# 11_5V_RAIL_ADC.net
KiCad netlist of a schematic drawn in Altium Designer
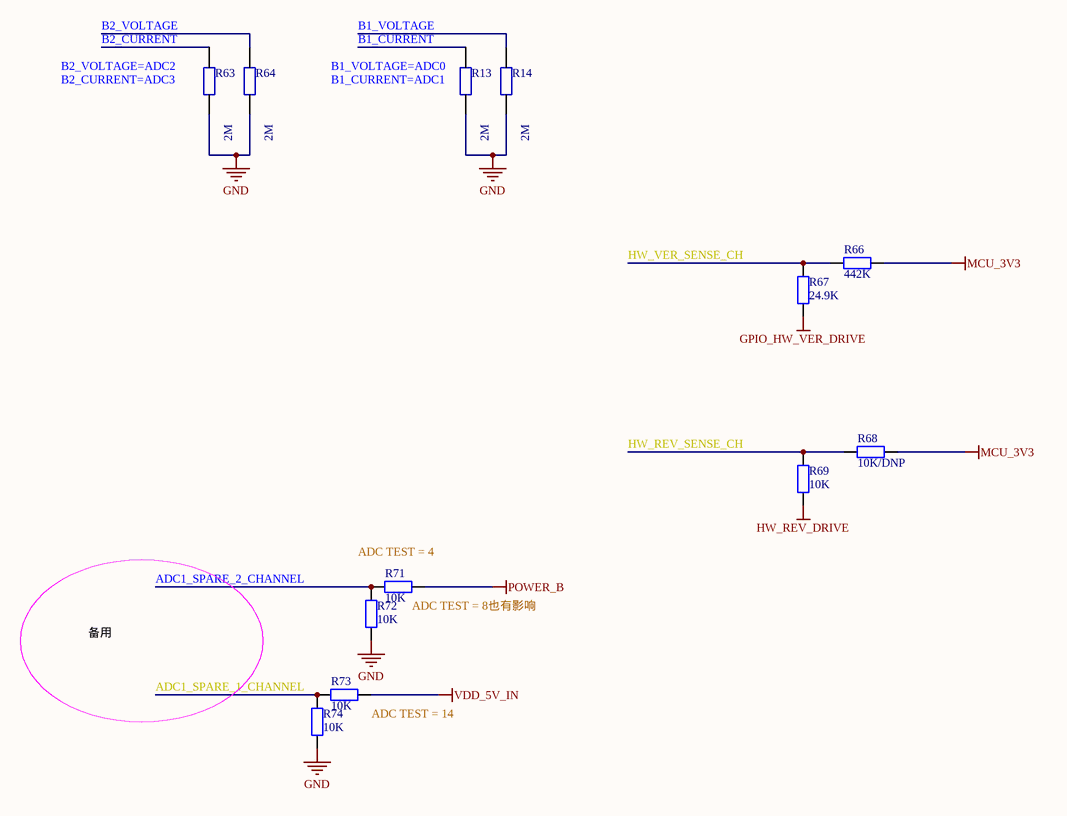
[diagram p0: 11_5V_RAIL_ADC.SchDoc]

(export (version "E")
  (design (tool "Eeschema 10.0.6"))
  (components
    (comp (ref "R13")
      (value "2M")
      (footprint "0402R")
      (description "0402R10K 1%")
      (libsource (lib "CUAV") (part "0402R10K"))
    )
    (comp (ref "R14")
      (value "2M")
      (footprint "0402R")
      (description "0402R10K 1%")
      (libsource (lib "CUAV") (part "0402R10K"))
    )
    (comp (ref "R63")
      (value "2M")
      (footprint "0402R")
      (description "0402R10K 1%")
      (libsource (lib "CUAV") (part "0402R10K"))
    )
    (comp (ref "R64")
      (value "2M")
      (footprint "0402R")
      (description "0402R10K 1%")
      (libsource (lib "CUAV") (part "0402R10K"))
    )
    (comp (ref "R66")
      (value "442K")
      (description "Resistor")
      (fields (field (name "PUBLISHER") "Altium Limited"))
      (libsource (lib "") (part "Res2_1"))
    )
    (comp (ref "R67")
      (value "24.9K")
      (description "Resistor")
      (fields (field (name "PUBLISHER") "Altium Limited"))
      (libsource (lib "Miscellaneous Devices") (part "Res2"))
    )
    (comp (ref "R68")
      (value "10K/DNP")
      (description "Resistor")
      (fields (field (name "PUBLISHER") "Altium Limited"))
      (libsource (lib "") (part "Res2_1"))
    )
    (comp (ref "R69")
      (value "10K")
      (description "Resistor")
      (fields (field (name "PUBLISHER") "Altium Limited"))
      (libsource (lib "Miscellaneous Devices") (part "Res2"))
    )
    (comp (ref "R71")
      (value "10K")
      (description "Resistor")
      (fields (field (name "PUBLISHER") "Altium Limited"))
      (libsource (lib "") (part "Res2_1"))
    )
    (comp (ref "R72")
      (value "10K")
      (description "Resistor")
      (fields (field (name "PUBLISHER") "Altium Limited"))
      (libsource (lib "Miscellaneous Devices") (part "Res2"))
    )
    (comp (ref "R73")
      (value "10K")
      (description "Resistor")
      (fields (field (name "PUBLISHER") "Altium Limited"))
      (libsource (lib "") (part "Res2_1"))
    )
    (comp (ref "R74")
      (value "10K")
      (description "Resistor")
      (fields (field (name "PUBLISHER") "Altium Limited"))
      (libsource (lib "Miscellaneous Devices") (part "Res2"))
    )
  )
  (nets
    (net (code "4") (name "/ADC1_SPARE_1_CHANNEL") (class "Default")
      (node (ref "R73") (pin "1") (pinfunction "1_1") (pintype "passive"))
      (node (ref "R74") (pin "2") (pinfunction "2_2") (pintype "passive"))
    )
    (net (code "5") (name "/ADC1_SPARE_2_CHANNEL") (class "Default")
      (node (ref "R71") (pin "1") (pinfunction "1_1") (pintype "passive"))
      (node (ref "R72") (pin "2") (pinfunction "2_2") (pintype "passive"))
    )
    (net (code "6") (name "/B1_CURRENT") (class "Default") (node (ref "R13") (pin "1") (pintype "passive")))
    (net (code "8") (name "/B1_VOLTAGE") (class "Default") (node (ref "R14") (pin "1") (pintype "passive")))
    (net (code "10") (name "/B2_CURRENT") (class "Default") (node (ref "R63") (pin "1") (pintype "passive")))
    (net (code "12") (name "/B2_VOLTAGE") (class "Default") (node (ref "R64") (pin "1") (pintype "passive")))
    (net (code "14") (name "/HW_REV_SENSE_CH") (class "Default")
      (node (ref "R68") (pin "1") (pinfunction "1_1") (pintype "passive"))
      (node (ref "R69") (pin "2") (pinfunction "2_2") (pintype "passive"))
    )
    (net (code "15") (name "/HW_VER_SENSE_CH") (class "Default")
      (node (ref "R66") (pin "1") (pinfunction "1_1") (pintype "passive"))
      (node (ref "R67") (pin "2") (pinfunction "2_2") (pintype "passive"))
    )
    (net (code "17") (name "GND") (class "Default")
      (node (ref "R13") (pin "2") (pintype "passive"))
      (node (ref "R14") (pin "2") (pintype "passive"))
      (node (ref "R63") (pin "2") (pintype "passive"))
      (node (ref "R64") (pin "2") (pintype "passive"))
      (node (ref "R72") (pin "1") (pinfunction "1_1") (pintype "passive"))
      (node (ref "R74") (pin "1") (pinfunction "1_1") (pintype "passive"))
    )
    (net (code "18") (name "GPIO_HW_VER_DRIVE") (class "Default")
      (node (ref "R67") (pin "1") (pinfunction "1_1") (pintype "passive"))
    )
    (net (code "19") (name "HW_REV_DRIVE") (class "Default")
      (node (ref "R69") (pin "1") (pinfunction "1_1") (pintype "passive"))
    )
    (net (code "20") (name "MCU_3V3") (class "Default")
      (node (ref "R66") (pin "2") (pinfunction "2_2") (pintype "passive"))
      (node (ref "R68") (pin "2") (pinfunction "2_2") (pintype "passive"))
    )
    (net (code "21") (name "POWER_B") (class "Default")
      (node (ref "R71") (pin "2") (pinfunction "2_2") (pintype "passive"))
    )
    (net (code "22") (name "VDD_5V_IN") (class "Default")
      (node (ref "R73") (pin "2") (pinfunction "2_2") (pintype "passive"))
    )
  )
)
